# MatrixDriver.net
KiCad netlist of a schematic drawn in EAGLE
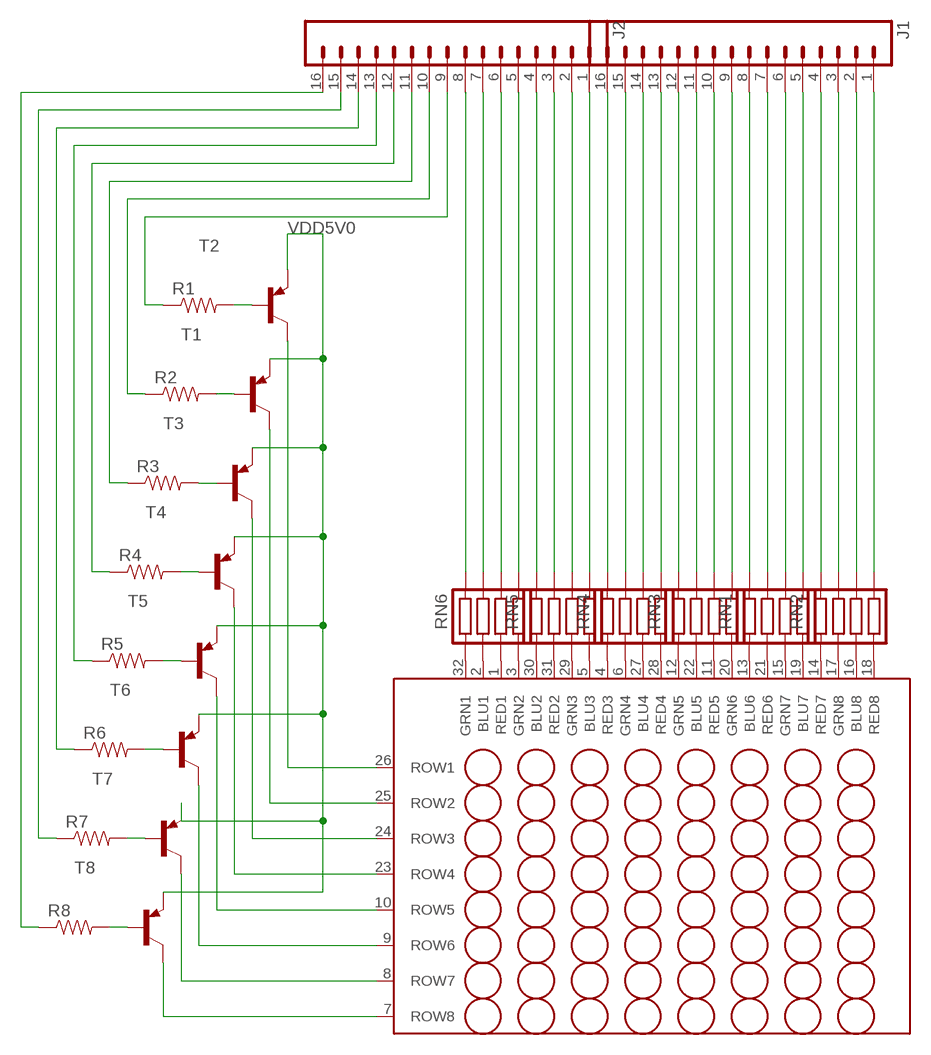
[diagram p0: schematic, sheet 1]

(export (version "E")
  (design (tool "Eeschema 10.0.6"))
  (components
    (comp (ref "J1")
      (value "M16DUAL_ROW")
      (footprint "eagle-import:2X8")
      (libsource (lib "eagle-import") (part "M16DUAL_ROW"))
    )
    (comp (ref "J2")
      (value "M16DUAL_ROW")
      (footprint "eagle-import:2X8")
      (libsource (lib "eagle-import") (part "M16DUAL_ROW"))
    )
    (comp (ref "R1")
      (value "RESISTOR0805-RES")
      (footprint "eagle-import:0805")
      (libsource (lib "eagle-import") (part "RESISTOR0805-RES"))
    )
    (comp (ref "R2")
      (value "RESISTOR0805-RES")
      (footprint "eagle-import:0805")
      (libsource (lib "eagle-import") (part "RESISTOR0805-RES"))
    )
    (comp (ref "R3")
      (value "RESISTOR0805-RES")
      (footprint "eagle-import:0805")
      (libsource (lib "eagle-import") (part "RESISTOR0805-RES"))
    )
    (comp (ref "R4")
      (value "RESISTOR0805-RES")
      (footprint "eagle-import:0805")
      (libsource (lib "eagle-import") (part "RESISTOR0805-RES"))
    )
    (comp (ref "R5")
      (value "RESISTOR0805-RES")
      (footprint "eagle-import:0805")
      (libsource (lib "eagle-import") (part "RESISTOR0805-RES"))
    )
    (comp (ref "R6")
      (value "RESISTOR0805-RES")
      (footprint "eagle-import:0805")
      (libsource (lib "eagle-import") (part "RESISTOR0805-RES"))
    )
    (comp (ref "R7")
      (value "RESISTOR0805-RES")
      (footprint "eagle-import:0805")
      (libsource (lib "eagle-import") (part "RESISTOR0805-RES"))
    )
    (comp (ref "R8")
      (value "RESISTOR0805-RES")
      (footprint "eagle-import:0805")
      (libsource (lib "eagle-import") (part "RESISTOR0805-RES"))
    )
    (comp (ref "RN1")
      (value "RESISTOR_ARRAY-4")
      (footprint "eagle-import:EXB-38V271JV")
      (libsource (lib "eagle-import") (part "RESISTOR_ARRAY-4"))
    )
    (comp (ref "RN2")
      (value "RESISTOR_ARRAY-4")
      (footprint "eagle-import:EXB-38V271JV")
      (libsource (lib "eagle-import") (part "RESISTOR_ARRAY-4"))
    )
    (comp (ref "RN3")
      (value "RESISTOR_ARRAY-4")
      (footprint "eagle-import:EXB-38V271JV")
      (libsource (lib "eagle-import") (part "RESISTOR_ARRAY-4"))
    )
    (comp (ref "RN4")
      (value "RESISTOR_ARRAY-4")
      (footprint "eagle-import:EXB-38V271JV")
      (libsource (lib "eagle-import") (part "RESISTOR_ARRAY-4"))
    )
    (comp (ref "RN5")
      (value "RESISTOR_ARRAY-4")
      (footprint "eagle-import:EXB-38V271JV")
      (libsource (lib "eagle-import") (part "RESISTOR_ARRAY-4"))
    )
    (comp (ref "RN6")
      (value "RESISTOR_ARRAY-4")
      (footprint "eagle-import:EXB-38V271JV")
      (libsource (lib "eagle-import") (part "RESISTOR_ARRAY-4"))
    )
    (comp (ref "T1")
      (value "2N3906-PNP-TO92-EBC")
      (footprint "eagle-import:TO92-EBC")
      (libsource (lib "eagle-import") (part "-PNP-TO92-EBC2N3906"))
    )
    (comp (ref "T2")
      (value "2N3906-PNP-TO92-EBC")
      (footprint "eagle-import:TO92-EBC")
      (libsource (lib "eagle-import") (part "-PNP-TO92-EBC2N3906"))
    )
    (comp (ref "T3")
      (value "2N3906-PNP-TO92-EBC")
      (footprint "eagle-import:TO92-EBC")
      (libsource (lib "eagle-import") (part "-PNP-TO92-EBC2N3906"))
    )
    (comp (ref "T4")
      (value "2N3906-PNP-TO92-EBC")
      (footprint "eagle-import:TO92-EBC")
      (libsource (lib "eagle-import") (part "-PNP-TO92-EBC2N3906"))
    )
    (comp (ref "T5")
      (value "2N3906-PNP-TO92-EBC")
      (footprint "eagle-import:TO92-EBC")
      (libsource (lib "eagle-import") (part "-PNP-TO92-EBC2N3906"))
    )
    (comp (ref "T6")
      (value "2N3906-PNP-TO92-EBC")
      (footprint "eagle-import:TO92-EBC")
      (libsource (lib "eagle-import") (part "-PNP-TO92-EBC2N3906"))
    )
    (comp (ref "T7")
      (value "2N3906-PNP-TO92-EBC")
      (footprint "eagle-import:TO92-EBC")
      (libsource (lib "eagle-import") (part "-PNP-TO92-EBC2N3906"))
    )
    (comp (ref "T8")
      (value "2N3906-PNP-TO92-EBC")
      (footprint "eagle-import:TO92-EBC")
      (libsource (lib "eagle-import") (part "-PNP-TO92-EBC2N3906"))
    )
    (comp (ref "U$1")
      (value "BL-M23B88RGB-11")
      (footprint "eagle-import:8X8RGBMATRIX")
      (libsource (lib "eagle-import") (part "BL-M23B88RGB-11"))
    )
  )
  (nets
    (net (code "1") (name "/VDD5V0") (class "Default")
      (node (ref "T1") (pin "E") (pinfunction "E_E") (pintype "passive"))
      (node (ref "T2") (pin "E") (pinfunction "E_E") (pintype "passive"))
      (node (ref "T3") (pin "E") (pinfunction "E_E") (pintype "passive"))
      (node (ref "T4") (pin "E") (pinfunction "E_E") (pintype "passive"))
      (node (ref "T5") (pin "E") (pinfunction "E_E") (pintype "passive"))
      (node (ref "T6") (pin "E") (pinfunction "E_E") (pintype "passive"))
      (node (ref "T7") (pin "E") (pinfunction "E_E") (pintype "passive"))
      (node (ref "T8") (pin "E") (pinfunction "E_E") (pintype "passive"))
    )
    (net (code "2") (name "Net-(J2-Pad9)") (class "Default")
      (node (ref "J2") (pin "9") (pinfunction "9_9") (pintype "passive"))
      (node (ref "R1") (pin "1") (pinfunction "1_1") (pintype "passive"))
    )
    (net (code "3") (name "Net-(J2-Pad10)") (class "Default")
      (node (ref "J2") (pin "10") (pinfunction "10_10") (pintype "passive"))
      (node (ref "R2") (pin "1") (pinfunction "1_1") (pintype "passive"))
    )
    (net (code "4") (name "Net-(J2-Pad11)") (class "Default")
      (node (ref "J2") (pin "11") (pinfunction "11_11") (pintype "passive"))
      (node (ref "R3") (pin "1") (pinfunction "1_1") (pintype "passive"))
    )
    (net (code "5") (name "Net-(J2-Pad12)") (class "Default")
      (node (ref "J2") (pin "12") (pinfunction "12_12") (pintype "passive"))
      (node (ref "R4") (pin "1") (pinfunction "1_1") (pintype "passive"))
    )
    (net (code "6") (name "Net-(J2-Pad13)") (class "Default")
      (node (ref "J2") (pin "13") (pinfunction "13_13") (pintype "passive"))
      (node (ref "R5") (pin "1") (pinfunction "1_1") (pintype "passive"))
    )
    (net (code "7") (name "Net-(J2-Pad14)") (class "Default")
      (node (ref "J2") (pin "14") (pinfunction "14_14") (pintype "passive"))
      (node (ref "R6") (pin "1") (pinfunction "1_1") (pintype "passive"))
    )
    (net (code "8") (name "Net-(J2-Pad15)") (class "Default")
      (node (ref "J2") (pin "15") (pinfunction "15_15") (pintype "passive"))
      (node (ref "R7") (pin "1") (pinfunction "1_1") (pintype "passive"))
    )
    (net (code "9") (name "Net-(J2-Pad16)") (class "Default")
      (node (ref "J2") (pin "16") (pinfunction "16_16") (pintype "passive"))
      (node (ref "R8") (pin "1") (pinfunction "1_1") (pintype "passive"))
    )
    (net (code "10") (name "Net-(R1-Pad2)") (class "Default")
      (node (ref "R1") (pin "2") (pinfunction "2_2") (pintype "passive"))
      (node (ref "T2") (pin "B") (pinfunction "B_B") (pintype "passive"))
    )
    (net (code "11") (name "Net-(R2-Pad2)") (class "Default")
      (node (ref "R2") (pin "2") (pinfunction "2_2") (pintype "passive"))
      (node (ref "T1") (pin "B") (pinfunction "B_B") (pintype "passive"))
    )
    (net (code "12") (name "Net-(R3-Pad2)") (class "Default")
      (node (ref "R3") (pin "2") (pinfunction "2_2") (pintype "passive"))
      (node (ref "T3") (pin "B") (pinfunction "B_B") (pintype "passive"))
    )
    (net (code "13") (name "Net-(R4-Pad2)") (class "Default")
      (node (ref "R4") (pin "2") (pinfunction "2_2") (pintype "passive"))
      (node (ref "T4") (pin "B") (pinfunction "B_B") (pintype "passive"))
    )
    (net (code "14") (name "Net-(R5-Pad2)") (class "Default")
      (node (ref "R5") (pin "2") (pinfunction "2_2") (pintype "passive"))
      (node (ref "T5") (pin "B") (pinfunction "B_B") (pintype "passive"))
    )
    (net (code "15") (name "Net-(R6-Pad2)") (class "Default")
      (node (ref "R6") (pin "2") (pinfunction "2_2") (pintype "passive"))
      (node (ref "T6") (pin "B") (pinfunction "B_B") (pintype "passive"))
    )
    (net (code "16") (name "Net-(R7-Pad2)") (class "Default")
      (node (ref "R7") (pin "2") (pinfunction "2_2") (pintype "passive"))
      (node (ref "T7") (pin "B") (pinfunction "B_B") (pintype "passive"))
    )
    (net (code "17") (name "Net-(R8-Pad2)") (class "Default")
      (node (ref "R8") (pin "2") (pinfunction "2_2") (pintype "passive"))
      (node (ref "T8") (pin "B") (pinfunction "B_B") (pintype "passive"))
    )
    (net (code "18") (name "Net-(RN1-1)") (class "Default")
      (node (ref "J1") (pin "8") (pinfunction "8_8") (pintype "passive"))
      (node (ref "RN1") (pin "P$1") (pinfunction "1_P$1") (pintype "passive"))
    )
    (net (code "19") (name "Net-(RN1-2)") (class "Default")
      (node (ref "J1") (pin "7") (pinfunction "7_7") (pintype "passive"))
      (node (ref "RN1") (pin "P$2") (pinfunction "2_P$2") (pintype "passive"))
    )
    (net (code "20") (name "Net-(RN1-3)") (class "Default")
      (node (ref "J1") (pin "6") (pinfunction "6_6") (pintype "passive"))
      (node (ref "RN1") (pin "P$3") (pinfunction "3_P$3") (pintype "passive"))
    )
    (net (code "21") (name "Net-(RN1-4)") (class "Default")
      (node (ref "J1") (pin "5") (pinfunction "5_5") (pintype "passive"))
      (node (ref "RN1") (pin "P$4") (pinfunction "4_P$4") (pintype "passive"))
    )
    (net (code "22") (name "Net-(RN1-5)") (class "Default")
      (node (ref "RN1") (pin "P$5") (pinfunction "5_P$5") (pintype "passive"))
      (node (ref "U$1") (pin "19") (pinfunction "BLU7_19") (pintype "bidirectional"))
    )
    (net (code "23") (name "Net-(RN1-6)") (class "Default")
      (node (ref "RN1") (pin "P$6") (pinfunction "6_P$6") (pintype "passive"))
      (node (ref "U$1") (pin "15") (pinfunction "GRN7_15") (pintype "bidirectional"))
    )
    (net (code "24") (name "Net-(RN1-7)") (class "Default")
      (node (ref "RN1") (pin "P$7") (pinfunction "7_P$7") (pintype "passive"))
      (node (ref "U$1") (pin "21") (pinfunction "RED6_21") (pintype "bidirectional"))
    )
    (net (code "25") (name "Net-(RN1-8)") (class "Default")
      (node (ref "RN1") (pin "P$8") (pinfunction "8_P$8") (pintype "passive"))
      (node (ref "U$1") (pin "13") (pinfunction "BLU6_13") (pintype "bidirectional"))
    )
    (net (code "26") (name "Net-(RN2-1)") (class "Default")
      (node (ref "J1") (pin "4") (pinfunction "4_4") (pintype "passive"))
      (node (ref "RN2") (pin "P$1") (pinfunction "1_P$1") (pintype "passive"))
    )
    (net (code "27") (name "Net-(RN2-2)") (class "Default")
      (node (ref "J1") (pin "3") (pinfunction "3_3") (pintype "passive"))
      (node (ref "RN2") (pin "P$2") (pinfunction "2_P$2") (pintype "passive"))
    )
    (net (code "28") (name "Net-(RN2-3)") (class "Default")
      (node (ref "J1") (pin "2") (pinfunction "2_2") (pintype "passive"))
      (node (ref "RN2") (pin "P$3") (pinfunction "3_P$3") (pintype "passive"))
    )
    (net (code "29") (name "Net-(RN2-4)") (class "Default")
      (node (ref "J1") (pin "1") (pinfunction "1_1") (pintype "passive"))
      (node (ref "RN2") (pin "P$4") (pinfunction "4_P$4") (pintype "passive"))
    )
    (net (code "30") (name "Net-(RN2-5)") (class "Default")
      (node (ref "RN2") (pin "P$5") (pinfunction "5_P$5") (pintype "passive"))
      (node (ref "U$1") (pin "18") (pinfunction "RED8_18") (pintype "bidirectional"))
    )
    (net (code "31") (name "Net-(RN2-6)") (class "Default")
      (node (ref "RN2") (pin "P$6") (pinfunction "6_P$6") (pintype "passive"))
      (node (ref "U$1") (pin "16") (pinfunction "BLU8_16") (pintype "bidirectional"))
    )
    (net (code "32") (name "Net-(RN2-7)") (class "Default")
      (node (ref "RN2") (pin "P$7") (pinfunction "7_P$7") (pintype "passive"))
      (node (ref "U$1") (pin "17") (pinfunction "GRN8_17") (pintype "bidirectional"))
    )
    (net (code "33") (name "Net-(RN2-8)") (class "Default")
      (node (ref "RN2") (pin "P$8") (pinfunction "8_P$8") (pintype "passive"))
      (node (ref "U$1") (pin "14") (pinfunction "RED7_14") (pintype "bidirectional"))
    )
    (net (code "34") (name "Net-(RN3-1)") (class "Default")
      (node (ref "J1") (pin "12") (pinfunction "12_12") (pintype "passive"))
      (node (ref "RN3") (pin "P$1") (pinfunction "1_P$1") (pintype "passive"))
    )
    (net (code "35") (name "Net-(RN3-2)") (class "Default")
      (node (ref "J1") (pin "11") (pinfunction "11_11") (pintype "passive"))
      (node (ref "RN3") (pin "P$2") (pinfunction "2_P$2") (pintype "passive"))
    )
    (net (code "36") (name "Net-(RN3-3)") (class "Default")
      (node (ref "J1") (pin "10") (pinfunction "10_10") (pintype "passive"))
      (node (ref "RN3") (pin "P$3") (pinfunction "3_P$3") (pintype "passive"))
    )
    (net (code "37") (name "Net-(RN3-4)") (class "Default")
      (node (ref "J1") (pin "9") (pinfunction "9_9") (pintype "passive"))
      (node (ref "RN3") (pin "P$4") (pinfunction "4_P$4") (pintype "passive"))
    )
    (net (code "38") (name "Net-(RN3-5)") (class "Default")
      (node (ref "RN3") (pin "P$5") (pinfunction "5_P$5") (pintype "passive"))
      (node (ref "U$1") (pin "20") (pinfunction "GRN6_20") (pintype "bidirectional"))
    )
    (net (code "39") (name "Net-(RN3-6)") (class "Default")
      (node (ref "RN3") (pin "P$6") (pinfunction "6_P$6") (pintype "passive"))
      (node (ref "U$1") (pin "11") (pinfunction "RED5_11") (pintype "bidirectional"))
    )
    (net (code "40") (name "Net-(RN3-7)") (class "Default")
      (node (ref "RN3") (pin "P$7") (pinfunction "7_P$7") (pintype "passive"))
      (node (ref "U$1") (pin "22") (pinfunction "BLU5_22") (pintype "bidirectional"))
    )
    (net (code "41") (name "Net-(RN3-8)") (class "Default")
      (node (ref "RN3") (pin "P$8") (pinfunction "8_P$8") (pintype "passive"))
      (node (ref "U$1") (pin "12") (pinfunction "GRN5_12") (pintype "bidirectional"))
    )
    (net (code "42") (name "Net-(RN4-1)") (class "Default")
      (node (ref "J1") (pin "16") (pinfunction "16_16") (pintype "passive"))
      (node (ref "RN4") (pin "P$1") (pinfunction "1_P$1") (pintype "passive"))
    )
    (net (code "43") (name "Net-(RN4-2)") (class "Default")
      (node (ref "J1") (pin "15") (pinfunction "15_15") (pintype "passive"))
      (node (ref "RN4") (pin "P$2") (pinfunction "2_P$2") (pintype "passive"))
    )
    (net (code "44") (name "Net-(RN4-3)") (class "Default")
      (node (ref "J1") (pin "14") (pinfunction "14_14") (pintype "passive"))
      (node (ref "RN4") (pin "P$3") (pinfunction "3_P$3") (pintype "passive"))
    )
    (net (code "45") (name "Net-(RN4-4)") (class "Default")
      (node (ref "J1") (pin "13") (pinfunction "13_13") (pintype "passive"))
      (node (ref "RN4") (pin "P$4") (pinfunction "4_P$4") (pintype "passive"))
    )
    (net (code "46") (name "Net-(RN4-5)") (class "Default")
      (node (ref "RN4") (pin "P$5") (pinfunction "5_P$5") (pintype "passive"))
      (node (ref "U$1") (pin "28") (pinfunction "RED4_28") (pintype "bidirectional"))
    )
    (net (code "47") (name "Net-(RN4-6)") (class "Default")
      (node (ref "RN4") (pin "P$6") (pinfunction "6_P$6") (pintype "passive"))
      (node (ref "U$1") (pin "27") (pinfunction "BLU4_27") (pintype "bidirectional"))
    )
    (net (code "48") (name "Net-(RN4-7)") (class "Default")
      (node (ref "RN4") (pin "P$7") (pinfunction "7_P$7") (pintype "passive"))
      (node (ref "U$1") (pin "6") (pinfunction "GRN4_6") (pintype "bidirectional"))
    )
    (net (code "49") (name "Net-(RN4-8)") (class "Default")
      (node (ref "RN4") (pin "P$8") (pinfunction "8_P$8") (pintype "passive"))
      (node (ref "U$1") (pin "4") (pinfunction "RED3_4") (pintype "bidirectional"))
    )
    (net (code "50") (name "Net-(RN5-1)") (class "Default")
      (node (ref "J2") (pin "4") (pinfunction "4_4") (pintype "passive"))
      (node (ref "RN5") (pin "P$1") (pinfunction "1_P$1") (pintype "passive"))
    )
    (net (code "51") (name "Net-(RN5-2)") (class "Default")
      (node (ref "J2") (pin "3") (pinfunction "3_3") (pintype "passive"))
      (node (ref "RN5") (pin "P$2") (pinfunction "2_P$2") (pintype "passive"))
    )
    (net (code "52") (name "Net-(RN5-3)") (class "Default")
      (node (ref "J2") (pin "2") (pinfunction "2_2") (pintype "passive"))
      (node (ref "RN5") (pin "P$3") (pinfunction "3_P$3") (pintype "passive"))
    )
    (net (code "53") (name "Net-(RN5-4)") (class "Default")
      (node (ref "J2") (pin "1") (pinfunction "1_1") (pintype "passive"))
      (node (ref "RN5") (pin "P$4") (pinfunction "4_P$4") (pintype "passive"))
    )
    (net (code "54") (name "Net-(RN5-5)") (class "Default")
      (node (ref "RN5") (pin "P$5") (pinfunction "5_P$5") (pintype "passive"))
      (node (ref "U$1") (pin "5") (pinfunction "BLU3_5") (pintype "bidirectional"))
    )
    (net (code "55") (name "Net-(RN5-6)") (class "Default")
      (node (ref "RN5") (pin "P$6") (pinfunction "6_P$6") (pintype "passive"))
      (node (ref "U$1") (pin "29") (pinfunction "GRN3_29") (pintype "bidirectional"))
    )
    (net (code "56") (name "Net-(RN5-7)") (class "Default")
      (node (ref "RN5") (pin "P$7") (pinfunction "7_P$7") (pintype "passive"))
      (node (ref "U$1") (pin "31") (pinfunction "RED2_31") (pintype "bidirectional"))
    )
    (net (code "57") (name "Net-(RN5-8)") (class "Default")
      (node (ref "RN5") (pin "P$8") (pinfunction "8_P$8") (pintype "passive"))
      (node (ref "U$1") (pin "30") (pinfunction "BLU2_30") (pintype "bidirectional"))
    )
    (net (code "58") (name "Net-(RN6-1)") (class "Default")
      (node (ref "J2") (pin "8") (pinfunction "8_8") (pintype "passive"))
      (node (ref "RN6") (pin "P$1") (pinfunction "1_P$1") (pintype "passive"))
    )
    (net (code "59") (name "Net-(RN6-2)") (class "Default")
      (node (ref "J2") (pin "7") (pinfunction "7_7") (pintype "passive"))
      (node (ref "RN6") (pin "P$2") (pinfunction "2_P$2") (pintype "passive"))
    )
    (net (code "60") (name "Net-(RN6-3)") (class "Default")
      (node (ref "J2") (pin "6") (pinfunction "6_6") (pintype "passive"))
      (node (ref "RN6") (pin "P$3") (pinfunction "3_P$3") (pintype "passive"))
    )
    (net (code "61") (name "Net-(RN6-4)") (class "Default")
      (node (ref "J2") (pin "5") (pinfunction "5_5") (pintype "passive"))
      (node (ref "RN6") (pin "P$4") (pinfunction "4_P$4") (pintype "passive"))
    )
    (net (code "62") (name "Net-(RN6-5)") (class "Default")
      (node (ref "RN6") (pin "P$5") (pinfunction "5_P$5") (pintype "passive"))
      (node (ref "U$1") (pin "3") (pinfunction "GRN2_3") (pintype "bidirectional"))
    )
    (net (code "63") (name "Net-(RN6-6)") (class "Default")
      (node (ref "RN6") (pin "P$6") (pinfunction "6_P$6") (pintype "passive"))
      (node (ref "U$1") (pin "1") (pinfunction "RED1_1") (pintype "bidirectional"))
    )
    (net (code "64") (name "Net-(RN6-7)") (class "Default")
      (node (ref "RN6") (pin "P$7") (pinfunction "7_P$7") (pintype "passive"))
      (node (ref "U$1") (pin "2") (pinfunction "BLU1_2") (pintype "bidirectional"))
    )
    (net (code "65") (name "Net-(RN6-8)") (class "Default")
      (node (ref "RN6") (pin "P$8") (pinfunction "8_P$8") (pintype "passive"))
      (node (ref "U$1") (pin "32") (pinfunction "GRN1_32") (pintype "bidirectional"))
    )
    (net (code "66") (name "Net-(U$1-ROW1)") (class "Default")
      (node (ref "T2") (pin "C") (pinfunction "C_C") (pintype "passive"))
      (node (ref "U$1") (pin "26") (pinfunction "ROW1_26") (pintype "bidirectional"))
    )
    (net (code "67") (name "Net-(U$1-ROW2)") (class "Default")
      (node (ref "T1") (pin "C") (pinfunction "C_C") (pintype "passive"))
      (node (ref "U$1") (pin "25") (pinfunction "ROW2_25") (pintype "bidirectional"))
    )
    (net (code "68") (name "Net-(U$1-ROW3)") (class "Default")
      (node (ref "T3") (pin "C") (pinfunction "C_C") (pintype "passive"))
      (node (ref "U$1") (pin "24") (pinfunction "ROW3_24") (pintype "bidirectional"))
    )
    (net (code "69") (name "Net-(U$1-ROW4)") (class "Default")
      (node (ref "T4") (pin "C") (pinfunction "C_C") (pintype "passive"))
      (node (ref "U$1") (pin "23") (pinfunction "ROW4_23") (pintype "bidirectional"))
    )
    (net (code "70") (name "Net-(U$1-ROW5)") (class "Default")
      (node (ref "T5") (pin "C") (pinfunction "C_C") (pintype "passive"))
      (node (ref "U$1") (pin "10") (pinfunction "ROW5_10") (pintype "bidirectional"))
    )
    (net (code "71") (name "Net-(U$1-ROW6)") (class "Default")
      (node (ref "T6") (pin "C") (pinfunction "C_C") (pintype "passive"))
      (node (ref "U$1") (pin "9") (pinfunction "ROW6_9") (pintype "bidirectional"))
    )
    (net (code "72") (name "Net-(U$1-ROW7)") (class "Default")
      (node (ref "T7") (pin "C") (pinfunction "C_C") (pintype "passive"))
      (node (ref "U$1") (pin "8") (pinfunction "ROW7_8") (pintype "bidirectional"))
    )
    (net (code "73") (name "Net-(U$1-ROW8)") (class "Default")
      (node (ref "T8") (pin "C") (pinfunction "C_C") (pintype "passive"))
      (node (ref "U$1") (pin "7") (pinfunction "ROW8_7") (pintype "bidirectional"))
    )
  )
)
